# ButtonBreakout.net
KiCad netlist of a schematic drawn in EAGLE
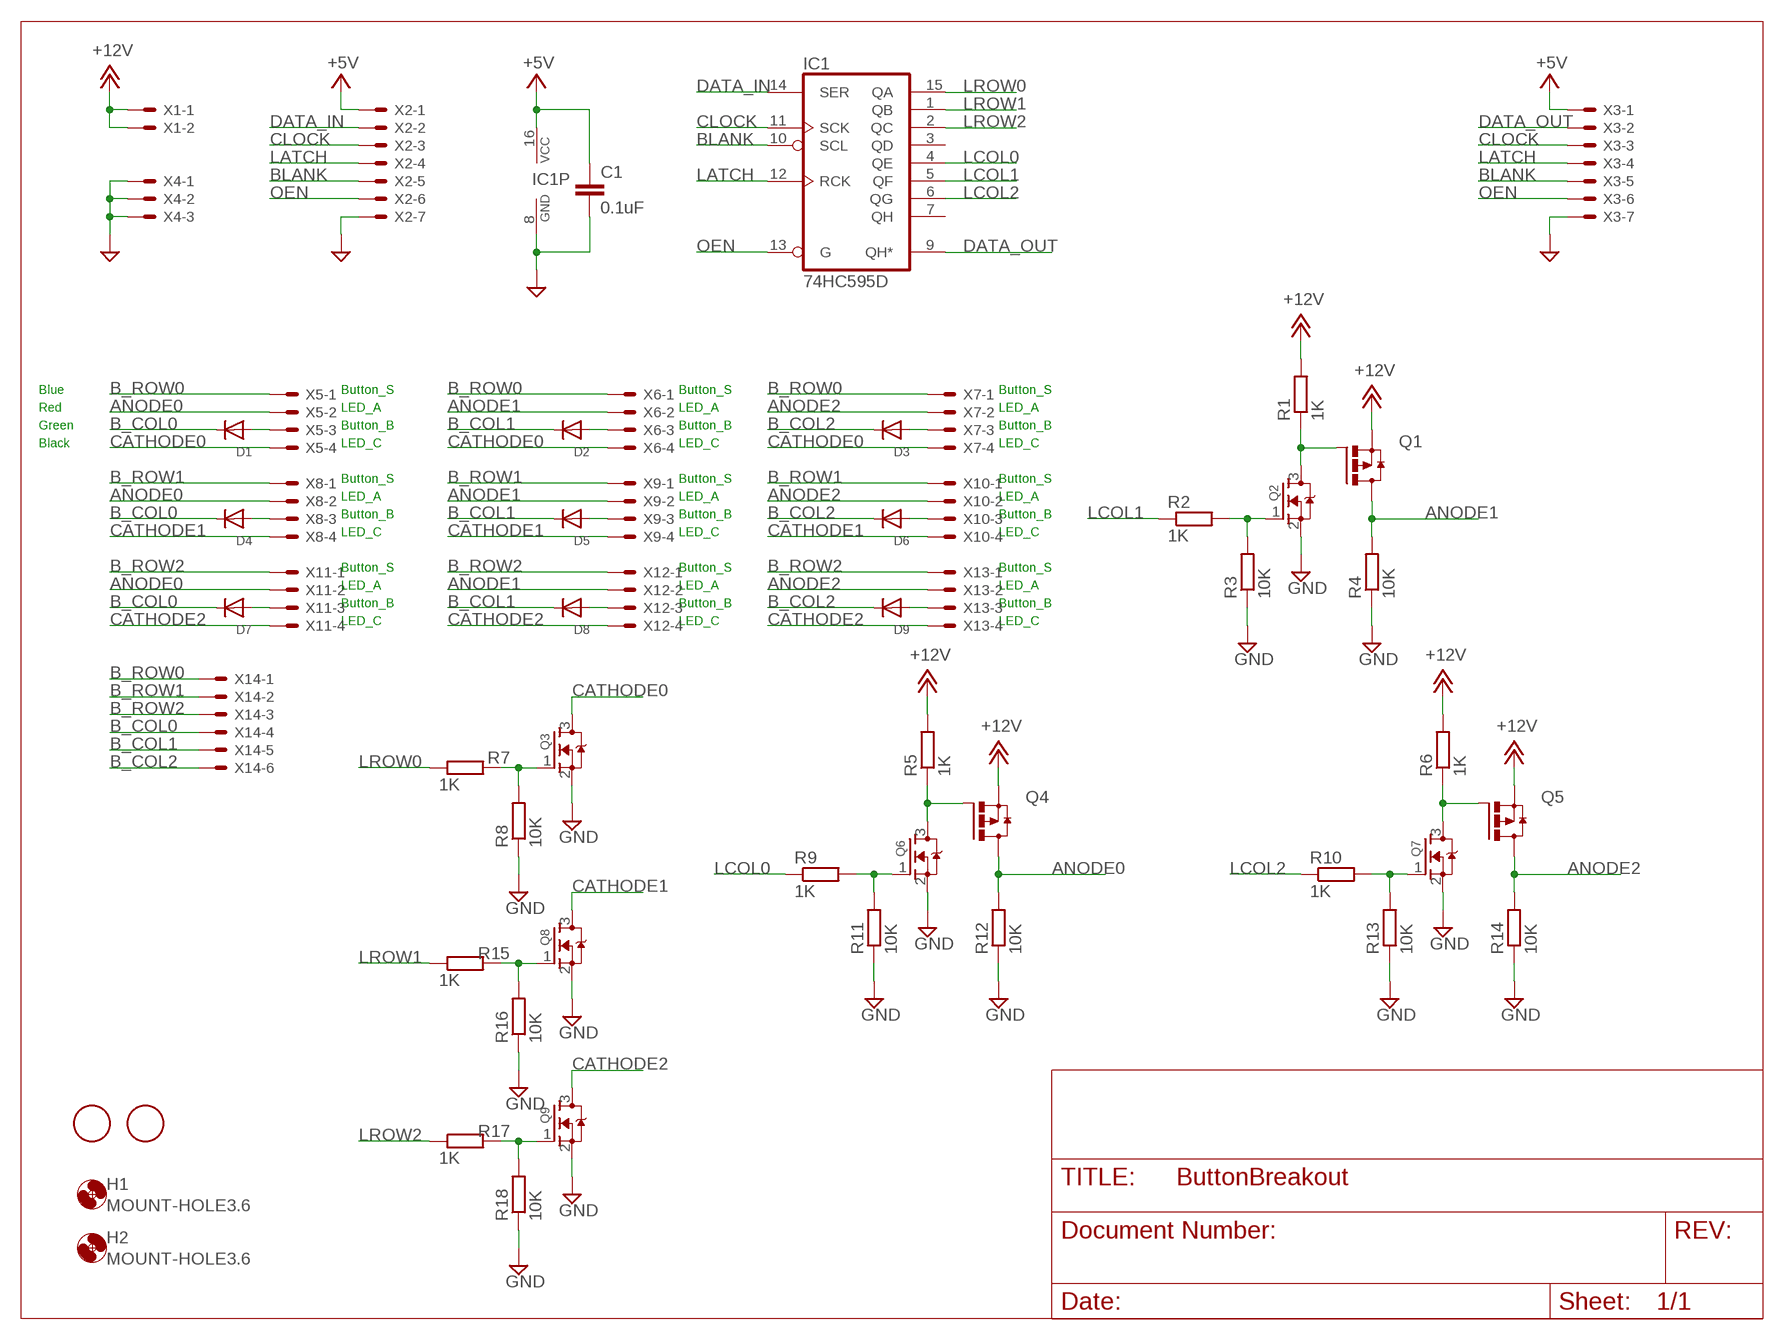
[diagram p0: schematic, sheet 1]

(export (version "E")
  (design (tool "Eeschema 10.0.6"))
  (components
    (comp (ref "C1")
      (value "0.1uF")
      (footprint "eagle-import:C0805")
      (libsource (lib "eagle-import") (part "C-EUC0805"))
    )
    (comp (ref "D1")
      (value "DIODESOD-123")
      (footprint "eagle-import:SOD-123")
      (libsource (lib "eagle-import") (part "DIODESOD-123"))
    )
    (comp (ref "D2")
      (value "DIODESOD-123")
      (footprint "eagle-import:SOD-123")
      (libsource (lib "eagle-import") (part "DIODESOD-123"))
    )
    (comp (ref "D3")
      (value "DIODESOD-123")
      (footprint "eagle-import:SOD-123")
      (libsource (lib "eagle-import") (part "DIODESOD-123"))
    )
    (comp (ref "D4")
      (value "DIODESOD-123")
      (footprint "eagle-import:SOD-123")
      (libsource (lib "eagle-import") (part "DIODESOD-123"))
    )
    (comp (ref "D5")
      (value "DIODESOD-123")
      (footprint "eagle-import:SOD-123")
      (libsource (lib "eagle-import") (part "DIODESOD-123"))
    )
    (comp (ref "D6")
      (value "DIODESOD-123")
      (footprint "eagle-import:SOD-123")
      (libsource (lib "eagle-import") (part "DIODESOD-123"))
    )
    (comp (ref "D7")
      (value "DIODESOD-123")
      (footprint "eagle-import:SOD-123")
      (libsource (lib "eagle-import") (part "DIODESOD-123"))
    )
    (comp (ref "D8")
      (value "DIODESOD-123")
      (footprint "eagle-import:SOD-123")
      (libsource (lib "eagle-import") (part "DIODESOD-123"))
    )
    (comp (ref "D9")
      (value "DIODESOD-123")
      (footprint "eagle-import:SOD-123")
      (libsource (lib "eagle-import") (part "DIODESOD-123"))
    )
    (comp (ref "F1")
      (value "FIDUCIAL")
      (footprint "eagle-import:FIDUCIAL_1MM")
      (libsource (lib "eagle-import") (part "FIDUCIAL"))
    )
    (comp (ref "F2")
      (value "FIDUCIAL")
      (footprint "eagle-import:FIDUCIAL_1MM")
      (libsource (lib "eagle-import") (part "FIDUCIAL"))
    )
    (comp (ref "H1")
      (value "MOUNT-HOLE3.6")
      (footprint "eagle-import:3,6")
      (libsource (lib "eagle-import") (part "MOUNT-HOLE3.6"))
    )
    (comp (ref "H2")
      (value "MOUNT-HOLE3.6")
      (footprint "eagle-import:3,6")
      (libsource (lib "eagle-import") (part "MOUNT-HOLE3.6"))
    )
    (comp (ref "IC1")
      (value "74HC595D")
      (footprint "eagle-import:SO16")
      (libsource (lib "eagle-import") (part "74595DHC"))
    )
    (comp (ref "Q1")
      (value "FDN360P")
      (footprint "eagle-import:SUPER-SOT3")
      (libsource (lib "eagle-import") (part "FDN360P"))
    )
    (comp (ref "Q2")
      (value "MOSFET-NREFLOW")
      (footprint "eagle-import:SOT23")
      (libsource (lib "eagle-import") (part "MOSFET-NREFLOW"))
    )
    (comp (ref "Q3")
      (value "MOSFET-NREFLOW")
      (footprint "eagle-import:SOT23")
      (libsource (lib "eagle-import") (part "MOSFET-NREFLOW"))
    )
    (comp (ref "Q4")
      (value "FDN360P")
      (footprint "eagle-import:SUPER-SOT3")
      (libsource (lib "eagle-import") (part "FDN360P"))
    )
    (comp (ref "Q5")
      (value "FDN360P")
      (footprint "eagle-import:SUPER-SOT3")
      (libsource (lib "eagle-import") (part "FDN360P"))
    )
    (comp (ref "Q6")
      (value "MOSFET-NREFLOW")
      (footprint "eagle-import:SOT23")
      (libsource (lib "eagle-import") (part "MOSFET-NREFLOW"))
    )
    (comp (ref "Q7")
      (value "MOSFET-NREFLOW")
      (footprint "eagle-import:SOT23")
      (libsource (lib "eagle-import") (part "MOSFET-NREFLOW"))
    )
    (comp (ref "Q8")
      (value "MOSFET-NREFLOW")
      (footprint "eagle-import:SOT23")
      (libsource (lib "eagle-import") (part "MOSFET-NREFLOW"))
    )
    (comp (ref "Q9")
      (value "MOSFET-NREFLOW")
      (footprint "eagle-import:SOT23")
      (libsource (lib "eagle-import") (part "MOSFET-NREFLOW"))
    )
    (comp (ref "R1")
      (value "1K")
      (footprint "eagle-import:R0805")
      (libsource (lib "eagle-import") (part "R-EU_R0805"))
    )
    (comp (ref "R2")
      (value "1K")
      (footprint "eagle-import:R0805")
      (libsource (lib "eagle-import") (part "R-EU_R0805"))
    )
    (comp (ref "R3")
      (value "10K")
      (footprint "eagle-import:R0805")
      (libsource (lib "eagle-import") (part "R-EU_R0805"))
    )
    (comp (ref "R4")
      (value "10K")
      (footprint "eagle-import:R0805")
      (libsource (lib "eagle-import") (part "R-EU_R0805"))
    )
    (comp (ref "R5")
      (value "1K")
      (footprint "eagle-import:R0805")
      (libsource (lib "eagle-import") (part "R-EU_R0805"))
    )
    (comp (ref "R6")
      (value "1K")
      (footprint "eagle-import:R0805")
      (libsource (lib "eagle-import") (part "R-EU_R0805"))
    )
    (comp (ref "R7")
      (value "1K")
      (footprint "eagle-import:R0805")
      (libsource (lib "eagle-import") (part "R-EU_R0805"))
    )
    (comp (ref "R8")
      (value "10K")
      (footprint "eagle-import:R0805")
      (libsource (lib "eagle-import") (part "R-EU_R0805"))
    )
    (comp (ref "R9")
      (value "1K")
      (footprint "eagle-import:R0805")
      (libsource (lib "eagle-import") (part "R-EU_R0805"))
    )
    (comp (ref "R10")
      (value "1K")
      (footprint "eagle-import:R0805")
      (libsource (lib "eagle-import") (part "R-EU_R0805"))
    )
    (comp (ref "R11")
      (value "10K")
      (footprint "eagle-import:R0805")
      (libsource (lib "eagle-import") (part "R-EU_R0805"))
    )
    (comp (ref "R12")
      (value "10K")
      (footprint "eagle-import:R0805")
      (libsource (lib "eagle-import") (part "R-EU_R0805"))
    )
    (comp (ref "R13")
      (value "10K")
      (footprint "eagle-import:R0805")
      (libsource (lib "eagle-import") (part "R-EU_R0805"))
    )
    (comp (ref "R14")
      (value "10K")
      (footprint "eagle-import:R0805")
      (libsource (lib "eagle-import") (part "R-EU_R0805"))
    )
    (comp (ref "R15")
      (value "1K")
      (footprint "eagle-import:R0805")
      (libsource (lib "eagle-import") (part "R-EU_R0805"))
    )
    (comp (ref "R16")
      (value "10K")
      (footprint "eagle-import:R0805")
      (libsource (lib "eagle-import") (part "R-EU_R0805"))
    )
    (comp (ref "R17")
      (value "1K")
      (footprint "eagle-import:R0805")
      (libsource (lib "eagle-import") (part "R-EU_R0805"))
    )
    (comp (ref "R18")
      (value "10K")
      (footprint "eagle-import:R0805")
      (libsource (lib "eagle-import") (part "R-EU_R0805"))
    )
    (comp (ref "X1")
      (value "JST-XH-02-PIN-LONG-PAD")
      (footprint "eagle-import:JST-XH-02-PACKAGE-LONG-PAD")
      (libsource (lib "eagle-import") (part "JST-XH-02-PIN-LONG-PAD"))
    )
    (comp (ref "X2")
      (value "JST-XH-07-PIN-LONG-PAD")
      (footprint "eagle-import:JST-XH-07-PACKAGE-LONG-PAD")
      (libsource (lib "eagle-import") (part "JST-XH-07-PIN-LONG-PAD"))
    )
    (comp (ref "X3")
      (value "JST-XH-07-PIN-LONG-PAD")
      (footprint "eagle-import:JST-XH-07-PACKAGE-LONG-PAD")
      (libsource (lib "eagle-import") (part "JST-XH-07-PIN-LONG-PAD"))
    )
    (comp (ref "X4")
      (value "JST-XH-03-PIN-LONG-PAD")
      (footprint "eagle-import:JST-XH-03-PACKAGE-LONG-PAD")
      (libsource (lib "eagle-import") (part "JST-XH-03-PIN-LONG-PAD"))
    )
    (comp (ref "X5")
      (value "JST-XH-04-PIN-LONG-PAD")
      (footprint "eagle-import:JST-XH-04-PACKAGE-LONG-PAD")
      (libsource (lib "eagle-import") (part "JST-XH-04-PIN-LONG-PAD"))
    )
    (comp (ref "X6")
      (value "JST-XH-04-PIN-LONG-PAD")
      (footprint "eagle-import:JST-XH-04-PACKAGE-LONG-PAD")
      (libsource (lib "eagle-import") (part "JST-XH-04-PIN-LONG-PAD"))
    )
    (comp (ref "X7")
      (value "JST-XH-04-PIN-LONG-PAD")
      (footprint "eagle-import:JST-XH-04-PACKAGE-LONG-PAD")
      (libsource (lib "eagle-import") (part "JST-XH-04-PIN-LONG-PAD"))
    )
    (comp (ref "X8")
      (value "JST-XH-04-PIN-LONG-PAD")
      (footprint "eagle-import:JST-XH-04-PACKAGE-LONG-PAD")
      (libsource (lib "eagle-import") (part "JST-XH-04-PIN-LONG-PAD"))
    )
    (comp (ref "X9")
      (value "JST-XH-04-PIN-LONG-PAD")
      (footprint "eagle-import:JST-XH-04-PACKAGE-LONG-PAD")
      (libsource (lib "eagle-import") (part "JST-XH-04-PIN-LONG-PAD"))
    )
    (comp (ref "X10")
      (value "JST-XH-04-PIN-LONG-PAD")
      (footprint "eagle-import:JST-XH-04-PACKAGE-LONG-PAD")
      (libsource (lib "eagle-import") (part "JST-XH-04-PIN-LONG-PAD"))
    )
    (comp (ref "X11")
      (value "JST-XH-04-PIN-LONG-PAD")
      (footprint "eagle-import:JST-XH-04-PACKAGE-LONG-PAD")
      (libsource (lib "eagle-import") (part "JST-XH-04-PIN-LONG-PAD"))
    )
    (comp (ref "X12")
      (value "JST-XH-04-PIN-LONG-PAD")
      (footprint "eagle-import:JST-XH-04-PACKAGE-LONG-PAD")
      (libsource (lib "eagle-import") (part "JST-XH-04-PIN-LONG-PAD"))
    )
    (comp (ref "X13")
      (value "JST-XH-04-PIN-LONG-PAD")
      (footprint "eagle-import:JST-XH-04-PACKAGE-LONG-PAD")
      (libsource (lib "eagle-import") (part "JST-XH-04-PIN-LONG-PAD"))
    )
    (comp (ref "X14")
      (value "JST-XH-06-PIN-LONG-PAD")
      (footprint "eagle-import:JST-XH-06-PACKAGE-LONG-PAD")
      (libsource (lib "eagle-import") (part "JST-XH-06-PIN-LONG-PAD"))
    )
  )
  (nets
    (net (code "1") (name "+5V") (class "Default")
      (node (ref "C1") (pin "1") (pinfunction "1_1") (pintype "passive"))
      (node (ref "IC1") (pin "16") (pinfunction "VCC_16") (pintype "power_in"))
      (node (ref "X2") (pin "1") (pinfunction "S_1") (pintype "passive"))
      (node (ref "X3") (pin "1") (pinfunction "S_1") (pintype "passive"))
    )
    (net (code "2") (name "+12V") (class "Default")
      (node (ref "Q1") (pin "2") (pinfunction "S_2") (pintype "passive"))
      (node (ref "Q4") (pin "2") (pinfunction "S_2") (pintype "passive"))
      (node (ref "Q5") (pin "2") (pinfunction "S_2") (pintype "passive"))
      (node (ref "R1") (pin "2") (pinfunction "2_2") (pintype "passive"))
      (node (ref "R5") (pin "2") (pinfunction "2_2") (pintype "passive"))
      (node (ref "R6") (pin "2") (pinfunction "2_2") (pintype "passive"))
      (node (ref "X1") (pin "1") (pinfunction "S_1") (pintype "passive"))
      (node (ref "X1") (pin "2") (pinfunction "S_2") (pintype "passive"))
    )
    (net (code "3") (name "/ANODE0") (class "Default")
      (node (ref "Q4") (pin "3") (pinfunction "D_3") (pintype "passive"))
      (node (ref "R12") (pin "2") (pinfunction "2_2") (pintype "passive"))
      (node (ref "X11") (pin "2") (pinfunction "S_2") (pintype "passive"))
      (node (ref "X5") (pin "2") (pinfunction "S_2") (pintype "passive"))
      (node (ref "X8") (pin "2") (pinfunction "S_2") (pintype "passive"))
    )
    (net (code "4") (name "/ANODE1") (class "Default")
      (node (ref "Q1") (pin "3") (pinfunction "D_3") (pintype "passive"))
      (node (ref "R4") (pin "2") (pinfunction "2_2") (pintype "passive"))
      (node (ref "X12") (pin "2") (pinfunction "S_2") (pintype "passive"))
      (node (ref "X6") (pin "2") (pinfunction "S_2") (pintype "passive"))
      (node (ref "X9") (pin "2") (pinfunction "S_2") (pintype "passive"))
    )
    (net (code "5") (name "/ANODE2") (class "Default")
      (node (ref "Q5") (pin "3") (pinfunction "D_3") (pintype "passive"))
      (node (ref "R14") (pin "2") (pinfunction "2_2") (pintype "passive"))
      (node (ref "X10") (pin "2") (pinfunction "S_2") (pintype "passive"))
      (node (ref "X13") (pin "2") (pinfunction "S_2") (pintype "passive"))
      (node (ref "X7") (pin "2") (pinfunction "S_2") (pintype "passive"))
    )
    (net (code "6") (name "/BLANK") (class "Default")
      (node (ref "IC1") (pin "10") (pinfunction "SCL_10") (pintype "input"))
      (node (ref "X2") (pin "5") (pinfunction "S_5") (pintype "passive"))
      (node (ref "X3") (pin "5") (pinfunction "S_5") (pintype "passive"))
    )
    (net (code "7") (name "/B_COL0") (class "Default")
      (node (ref "D1") (pin "C") (pinfunction "C_C") (pintype "passive"))
      (node (ref "D4") (pin "C") (pinfunction "C_C") (pintype "passive"))
      (node (ref "D7") (pin "C") (pinfunction "C_C") (pintype "passive"))
      (node (ref "X14") (pin "4") (pinfunction "S_4") (pintype "passive"))
    )
    (net (code "8") (name "/B_COL1") (class "Default")
      (node (ref "D2") (pin "C") (pinfunction "C_C") (pintype "passive"))
      (node (ref "D5") (pin "C") (pinfunction "C_C") (pintype "passive"))
      (node (ref "D8") (pin "C") (pinfunction "C_C") (pintype "passive"))
      (node (ref "X14") (pin "5") (pinfunction "S_5") (pintype "passive"))
    )
    (net (code "9") (name "/B_COL2") (class "Default")
      (node (ref "D3") (pin "C") (pinfunction "C_C") (pintype "passive"))
      (node (ref "D6") (pin "C") (pinfunction "C_C") (pintype "passive"))
      (node (ref "D9") (pin "C") (pinfunction "C_C") (pintype "passive"))
      (node (ref "X14") (pin "6") (pinfunction "S_6") (pintype "passive"))
    )
    (net (code "10") (name "/B_ROW0") (class "Default")
      (node (ref "X14") (pin "1") (pinfunction "S_1") (pintype "passive"))
      (node (ref "X5") (pin "1") (pinfunction "S_1") (pintype "passive"))
      (node (ref "X6") (pin "1") (pinfunction "S_1") (pintype "passive"))
      (node (ref "X7") (pin "1") (pinfunction "S_1") (pintype "passive"))
    )
    (net (code "11") (name "/B_ROW1") (class "Default")
      (node (ref "X10") (pin "1") (pinfunction "S_1") (pintype "passive"))
      (node (ref "X14") (pin "2") (pinfunction "S_2") (pintype "passive"))
      (node (ref "X8") (pin "1") (pinfunction "S_1") (pintype "passive"))
      (node (ref "X9") (pin "1") (pinfunction "S_1") (pintype "passive"))
    )
    (net (code "12") (name "/B_ROW2") (class "Default")
      (node (ref "X11") (pin "1") (pinfunction "S_1") (pintype "passive"))
      (node (ref "X12") (pin "1") (pinfunction "S_1") (pintype "passive"))
      (node (ref "X13") (pin "1") (pinfunction "S_1") (pintype "passive"))
      (node (ref "X14") (pin "3") (pinfunction "S_3") (pintype "passive"))
    )
    (net (code "13") (name "/CATHODE0") (class "Default")
      (node (ref "Q3") (pin "3") (pinfunction "D_3") (pintype "bidirectional"))
      (node (ref "X5") (pin "4") (pinfunction "S_4") (pintype "passive"))
      (node (ref "X6") (pin "4") (pinfunction "S_4") (pintype "passive"))
      (node (ref "X7") (pin "4") (pinfunction "S_4") (pintype "passive"))
    )
    (net (code "14") (name "/CATHODE1") (class "Default")
      (node (ref "Q8") (pin "3") (pinfunction "D_3") (pintype "bidirectional"))
      (node (ref "X10") (pin "4") (pinfunction "S_4") (pintype "passive"))
      (node (ref "X8") (pin "4") (pinfunction "S_4") (pintype "passive"))
      (node (ref "X9") (pin "4") (pinfunction "S_4") (pintype "passive"))
    )
    (net (code "15") (name "/CATHODE2") (class "Default")
      (node (ref "Q9") (pin "3") (pinfunction "D_3") (pintype "bidirectional"))
      (node (ref "X11") (pin "4") (pinfunction "S_4") (pintype "passive"))
      (node (ref "X12") (pin "4") (pinfunction "S_4") (pintype "passive"))
      (node (ref "X13") (pin "4") (pinfunction "S_4") (pintype "passive"))
    )
    (net (code "16") (name "/CLOCK") (class "Default")
      (node (ref "IC1") (pin "11") (pinfunction "SCK_11") (pintype "input"))
      (node (ref "X2") (pin "3") (pinfunction "S_3") (pintype "passive"))
      (node (ref "X3") (pin "3") (pinfunction "S_3") (pintype "passive"))
    )
    (net (code "17") (name "/DATA_IN") (class "Default")
      (node (ref "IC1") (pin "14") (pinfunction "SER_14") (pintype "input"))
      (node (ref "X2") (pin "2") (pinfunction "S_2") (pintype "passive"))
    )
    (net (code "18") (name "/DATA_OUT") (class "Default")
      (node (ref "IC1") (pin "9") (pinfunction "QH*_9") (pintype "tri_state"))
      (node (ref "X3") (pin "2") (pinfunction "S_2") (pintype "passive"))
    )
    (net (code "19") (name "/LATCH") (class "Default")
      (node (ref "IC1") (pin "12") (pinfunction "RCK_12") (pintype "input"))
      (node (ref "X2") (pin "4") (pinfunction "S_4") (pintype "passive"))
      (node (ref "X3") (pin "4") (pinfunction "S_4") (pintype "passive"))
    )
    (net (code "20") (name "/LCOL0") (class "Default")
      (node (ref "IC1") (pin "4") (pinfunction "QE_4") (pintype "tri_state"))
      (node (ref "R9") (pin "1") (pinfunction "1_1") (pintype "passive"))
    )
    (net (code "21") (name "/LCOL1") (class "Default")
      (node (ref "IC1") (pin "5") (pinfunction "QF_5") (pintype "tri_state"))
      (node (ref "R2") (pin "1") (pinfunction "1_1") (pintype "passive"))
    )
    (net (code "22") (name "/LCOL2") (class "Default")
      (node (ref "IC1") (pin "6") (pinfunction "QG_6") (pintype "tri_state"))
      (node (ref "R10") (pin "1") (pinfunction "1_1") (pintype "passive"))
    )
    (net (code "23") (name "/LROW0") (class "Default")
      (node (ref "IC1") (pin "15") (pinfunction "QA_15") (pintype "tri_state"))
      (node (ref "R7") (pin "1") (pinfunction "1_1") (pintype "passive"))
    )
    (net (code "24") (name "/LROW1") (class "Default")
      (node (ref "IC1") (pin "1") (pinfunction "QB_1") (pintype "tri_state"))
      (node (ref "R15") (pin "1") (pinfunction "1_1") (pintype "passive"))
    )
    (net (code "25") (name "/LROW2") (class "Default")
      (node (ref "IC1") (pin "2") (pinfunction "QC_2") (pintype "tri_state"))
      (node (ref "R17") (pin "1") (pinfunction "1_1") (pintype "passive"))
    )
    (net (code "26") (name "/OEN") (class "Default")
      (node (ref "IC1") (pin "13") (pinfunction "G_13") (pintype "input"))
      (node (ref "X2") (pin "6") (pinfunction "S_6") (pintype "passive"))
      (node (ref "X3") (pin "6") (pinfunction "S_6") (pintype "passive"))
    )
    (net (code "27") (name "GND") (class "Default")
      (node (ref "C1") (pin "2") (pinfunction "2_2") (pintype "passive"))
      (node (ref "IC1") (pin "8") (pinfunction "GND_8") (pintype "power_in"))
      (node (ref "Q2") (pin "2") (pinfunction "S_2") (pintype "bidirectional"))
      (node (ref "Q3") (pin "2") (pinfunction "S_2") (pintype "bidirectional"))
      (node (ref "Q6") (pin "2") (pinfunction "S_2") (pintype "bidirectional"))
      (node (ref "Q7") (pin "2") (pinfunction "S_2") (pintype "bidirectional"))
      (node (ref "Q8") (pin "2") (pinfunction "S_2") (pintype "bidirectional"))
      (node (ref "Q9") (pin "2") (pinfunction "S_2") (pintype "bidirectional"))
      (node (ref "R11") (pin "1") (pinfunction "1_1") (pintype "passive"))
      (node (ref "R12") (pin "1") (pinfunction "1_1") (pintype "passive"))
      (node (ref "R13") (pin "1") (pinfunction "1_1") (pintype "passive"))
      (node (ref "R14") (pin "1") (pinfunction "1_1") (pintype "passive"))
      (node (ref "R16") (pin "1") (pinfunction "1_1") (pintype "passive"))
      (node (ref "R18") (pin "1") (pinfunction "1_1") (pintype "passive"))
      (node (ref "R3") (pin "1") (pinfunction "1_1") (pintype "passive"))
      (node (ref "R4") (pin "1") (pinfunction "1_1") (pintype "passive"))
      (node (ref "R8") (pin "1") (pinfunction "1_1") (pintype "passive"))
      (node (ref "X2") (pin "7") (pinfunction "S_7") (pintype "passive"))
      (node (ref "X3") (pin "7") (pinfunction "S_7") (pintype "passive"))
      (node (ref "X4") (pin "1") (pinfunction "S_1") (pintype "passive"))
      (node (ref "X4") (pin "2") (pinfunction "S_2") (pintype "passive"))
      (node (ref "X4") (pin "3") (pinfunction "S_3") (pintype "passive"))
    )
    (net (code "28") (name "Net-(Q1-G)") (class "Default")
      (node (ref "Q1") (pin "1") (pinfunction "G_1") (pintype "passive"))
      (node (ref "Q2") (pin "3") (pinfunction "D_3") (pintype "bidirectional"))
      (node (ref "R1") (pin "1") (pinfunction "1_1") (pintype "passive"))
    )
    (net (code "29") (name "Net-(Q2-G)") (class "Default")
      (node (ref "Q2") (pin "1") (pinfunction "G_1") (pintype "bidirectional"))
      (node (ref "R2") (pin "2") (pinfunction "2_2") (pintype "passive"))
      (node (ref "R3") (pin "2") (pinfunction "2_2") (pintype "passive"))
    )
    (net (code "30") (name "Net-(Q3-G)") (class "Default")
      (node (ref "Q3") (pin "1") (pinfunction "G_1") (pintype "bidirectional"))
      (node (ref "R7") (pin "2") (pinfunction "2_2") (pintype "passive"))
      (node (ref "R8") (pin "2") (pinfunction "2_2") (pintype "passive"))
    )
    (net (code "31") (name "Net-(Q4-G)") (class "Default")
      (node (ref "Q4") (pin "1") (pinfunction "G_1") (pintype "passive"))
      (node (ref "Q6") (pin "3") (pinfunction "D_3") (pintype "bidirectional"))
      (node (ref "R5") (pin "1") (pinfunction "1_1") (pintype "passive"))
    )
    (net (code "32") (name "Net-(Q5-G)") (class "Default")
      (node (ref "Q5") (pin "1") (pinfunction "G_1") (pintype "passive"))
      (node (ref "Q7") (pin "3") (pinfunction "D_3") (pintype "bidirectional"))
      (node (ref "R6") (pin "1") (pinfunction "1_1") (pintype "passive"))
    )
    (net (code "33") (name "Net-(Q6-G)") (class "Default")
      (node (ref "Q6") (pin "1") (pinfunction "G_1") (pintype "bidirectional"))
      (node (ref "R11") (pin "2") (pinfunction "2_2") (pintype "passive"))
      (node (ref "R9") (pin "2") (pinfunction "2_2") (pintype "passive"))
    )
    (net (code "34") (name "Net-(Q7-G)") (class "Default")
      (node (ref "Q7") (pin "1") (pinfunction "G_1") (pintype "bidirectional"))
      (node (ref "R10") (pin "2") (pinfunction "2_2") (pintype "passive"))
      (node (ref "R13") (pin "2") (pinfunction "2_2") (pintype "passive"))
    )
    (net (code "35") (name "Net-(Q8-G)") (class "Default")
      (node (ref "Q8") (pin "1") (pinfunction "G_1") (pintype "bidirectional"))
      (node (ref "R15") (pin "2") (pinfunction "2_2") (pintype "passive"))
      (node (ref "R16") (pin "2") (pinfunction "2_2") (pintype "passive"))
    )
    (net (code "36") (name "Net-(Q9-G)") (class "Default")
      (node (ref "Q9") (pin "1") (pinfunction "G_1") (pintype "bidirectional"))
      (node (ref "R17") (pin "2") (pinfunction "2_2") (pintype "passive"))
      (node (ref "R18") (pin "2") (pinfunction "2_2") (pintype "passive"))
    )
    (net (code "37") (name "Net-(X5C-S)") (class "Default")
      (node (ref "D1") (pin "A") (pinfunction "A_A") (pintype "passive"))
      (node (ref "X5") (pin "3") (pinfunction "S_3") (pintype "passive"))
    )
    (net (code "38") (name "Net-(X6C-S)") (class "Default")
      (node (ref "D2") (pin "A") (pinfunction "A_A") (pintype "passive"))
      (node (ref "X6") (pin "3") (pinfunction "S_3") (pintype "passive"))
    )
    (net (code "39") (name "Net-(X7C-S)") (class "Default")
      (node (ref "D3") (pin "A") (pinfunction "A_A") (pintype "passive"))
      (node (ref "X7") (pin "3") (pinfunction "S_3") (pintype "passive"))
    )
    (net (code "40") (name "Net-(X8C-S)") (class "Default")
      (node (ref "D4") (pin "A") (pinfunction "A_A") (pintype "passive"))
      (node (ref "X8") (pin "3") (pinfunction "S_3") (pintype "passive"))
    )
    (net (code "41") (name "Net-(X9C-S)") (class "Default")
      (node (ref "D5") (pin "A") (pinfunction "A_A") (pintype "passive"))
      (node (ref "X9") (pin "3") (pinfunction "S_3") (pintype "passive"))
    )
    (net (code "42") (name "Net-(X10C-S)") (class "Default")
      (node (ref "D6") (pin "A") (pinfunction "A_A") (pintype "passive"))
      (node (ref "X10") (pin "3") (pinfunction "S_3") (pintype "passive"))
    )
    (net (code "43") (name "Net-(X11C-S)") (class "Default")
      (node (ref "D7") (pin "A") (pinfunction "A_A") (pintype "passive"))
      (node (ref "X11") (pin "3") (pinfunction "S_3") (pintype "passive"))
    )
    (net (code "44") (name "Net-(X12C-S)") (class "Default")
      (node (ref "D8") (pin "A") (pinfunction "A_A") (pintype "passive"))
      (node (ref "X12") (pin "3") (pinfunction "S_3") (pintype "passive"))
    )
    (net (code "45") (name "Net-(X13C-S)") (class "Default")
      (node (ref "D9") (pin "A") (pinfunction "A_A") (pintype "passive"))
      (node (ref "X13") (pin "3") (pinfunction "S_3") (pintype "passive"))
    )
    (net (code "46") (name "unconnected-(IC1A-QD-Pad3)") (class "Default")
      (node (ref "IC1") (pin "3") (pinfunction "QD_3") (pintype "tri_state"))
    )
    (net (code "47") (name "unconnected-(IC1A-QH-Pad7)") (class "Default")
      (node (ref "IC1") (pin "7") (pinfunction "QH_7") (pintype "tri_state"))
    )
  )
)
